# DAM16_Ethernet.net
KiCad netlist of a schematic drawn in Altium Designer
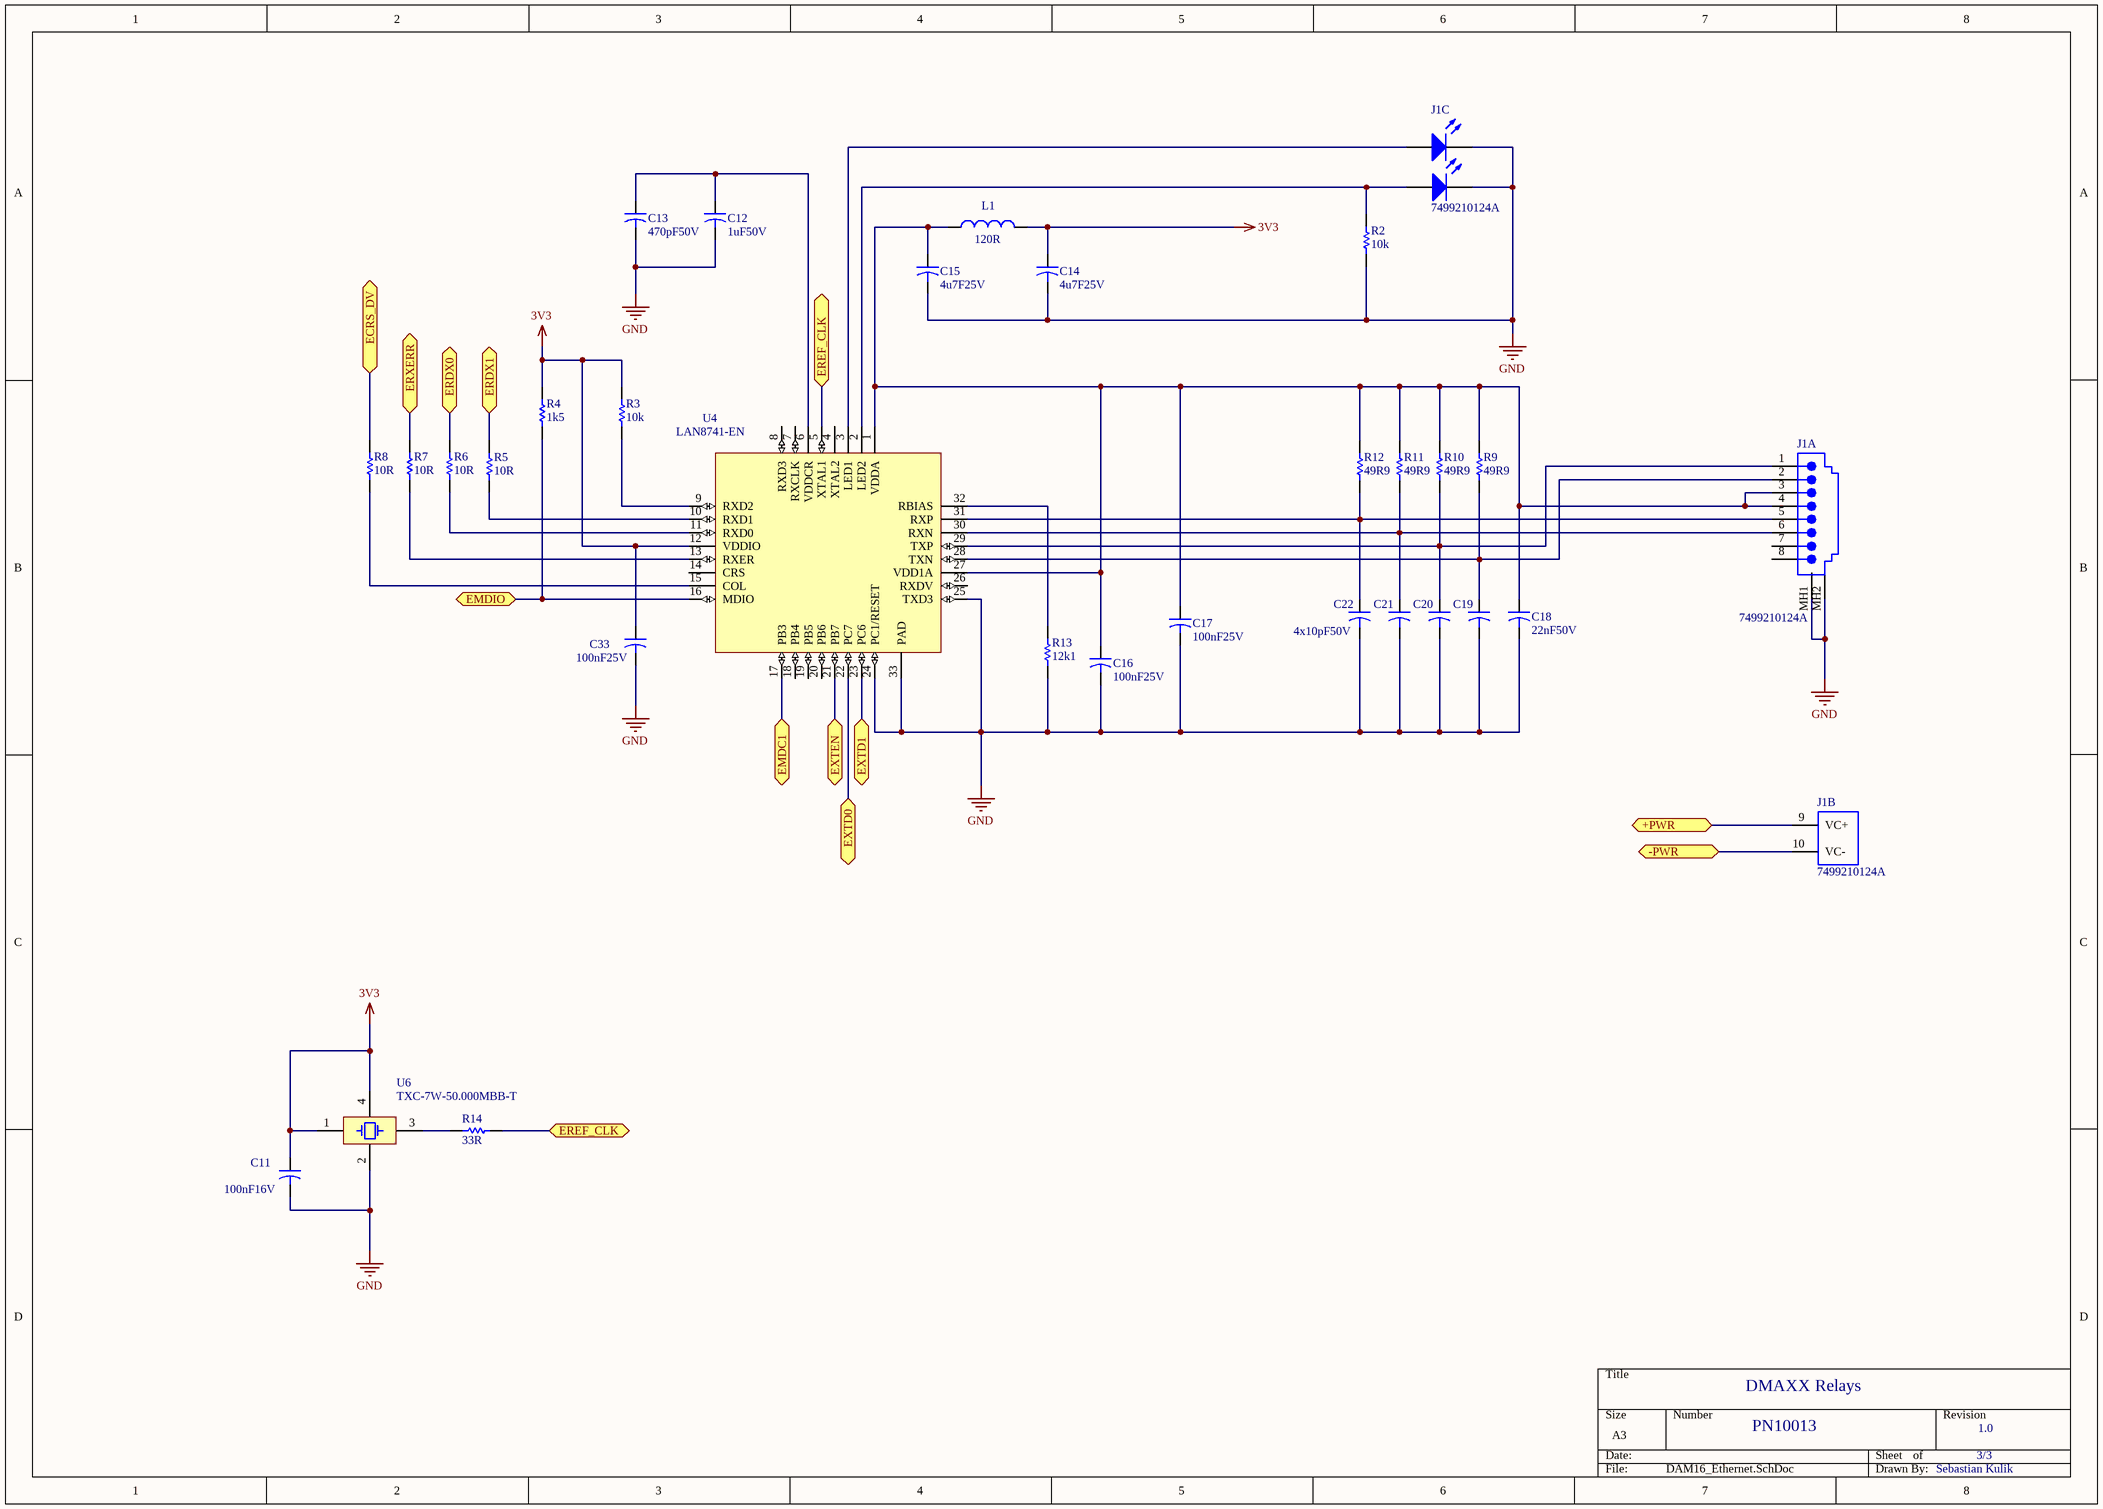
[diagram p0: DAM16_Ethernet.SchDoc]

(export (version "E")
  (design (tool "Eeschema 10.0.6"))
  (components
    (comp (ref "C11")
      (value "100nF16V")
      (footprint "C0402")
      (description "Capacitor")
      (fields
        (field (name "MANUFACTURER") "TDK")
        (field (name "Comment") "100nF16V_0402")
        (field (name "PUBLISHER") "Sebastian Kulik")
      )
      (libsource (lib "Capacitors") (part "100nF16V_0402"))
    )
    (comp (ref "C12")
      (value "1uF50V")
      (footprint "C0603")
      (description "C series, X5R, 10%")
      (fields
        (field (name "MANUFACTURER") "TDK")
        (field (name "Comment") "1uF50V_0603")
        (field (name "PUBLISHER") "Sebastian Kulik")
      )
      (libsource (lib "Capacitors") (part "1uF50V_0603"))
    )
    (comp (ref "C13")
      (value "470pF50V")
      (footprint "C0402")
      (description "AVX, 50V")
      (fields
        (field (name "MANUFACTURER") "AVX")
        (field (name "Comment") "470pF50V_0402")
        (field (name "PUBLISHER") "Sebastian Kulik")
      )
      (libsource (lib "Capacitors") (part "470pF50V_0402"))
    )
    (comp (ref "C14")
      (value "4u7F25V")
      (footprint "C0805")
      (description "TDK  C series, X7R, 10%, 25V")
      (fields
        (field (name "MANUFACTURER") "TDK")
        (field (name "Comment") "4u7F25V_0805")
        (field (name "PUBLISHER") "Sebastian Kulik")
      )
      (libsource (lib "Capacitors") (part "4u7F25V_0805"))
    )
    (comp (ref "C15")
      (value "4u7F25V")
      (footprint "C0805")
      (description "TDK  C series, X7R, 10%, 25V")
      (fields
        (field (name "MANUFACTURER") "TDK")
        (field (name "Comment") "4u7F25V_0805")
        (field (name "PUBLISHER") "Sebastian Kulik")
      )
      (libsource (lib "Capacitors") (part "4u7F25V_0805"))
    )
    (comp (ref "C16")
      (value "100nF25V")
      (footprint "C0402")
      (description "AVX, X5R, 10%, 25V")
      (fields
        (field (name "MANUFACTURER") "AVX")
        (field (name "Comment") "100nF25V_0402")
        (field (name "PUBLISHER") "Sebastian Kulik")
      )
      (libsource (lib "Capacitors") (part "100nF25V_0402"))
    )
    (comp (ref "C17")
      (value "100nF25V")
      (footprint "C0402")
      (description "AVX, X5R, 10%, 25V")
      (fields
        (field (name "MANUFACTURER") "AVX")
        (field (name "Comment") "100nF25V_0402")
        (field (name "PUBLISHER") "Sebastian Kulik")
      )
      (libsource (lib "Capacitors") (part "100nF25V_0402"))
    )
    (comp (ref "C18")
      (value "22nF50V")
      (footprint "C0603")
      (description "AVX ,  X7R, 5%, 50V")
      (fields
        (field (name "MANUFACTURER") "AVX")
        (field (name "Comment") "22nF50V_0603")
        (field (name "PUBLISHER") "Sebastian Kulik")
      )
      (libsource (lib "Capacitors") (part "22nF50V_0603"))
    )
    (comp (ref "C19")
      (value "10pF50V_0603")
      (footprint "C0603")
      (description "AVX ,  +-0.5pF, 50V")
      (fields (field (name "MANUFACTURER") "AVX") (field (name "PUBLISHER") "Sebastian Kulik"))
      (libsource (lib "Capacitors") (part "10pF50V_0603"))
    )
    (comp (ref "C20")
      (value "10pF50V_0603")
      (footprint "C0603")
      (description "AVX ,  +-0.5pF, 50V")
      (fields (field (name "MANUFACTURER") "AVX") (field (name "PUBLISHER") "Sebastian Kulik"))
      (libsource (lib "Capacitors") (part "10pF50V_0603"))
    )
    (comp (ref "C21")
      (value "10pF50V_0603")
      (footprint "C0603")
      (description "AVX ,  +-0.5pF, 50V")
      (fields (field (name "MANUFACTURER") "AVX") (field (name "PUBLISHER") "Sebastian Kulik"))
      (libsource (lib "Capacitors") (part "10pF50V_0603"))
    )
    (comp (ref "C22")
      (value "10pF50V_0603")
      (footprint "C0603")
      (description "AVX ,  +-0.5pF, 50V")
      (fields (field (name "MANUFACTURER") "AVX") (field (name "PUBLISHER") "Sebastian Kulik"))
      (libsource (lib "Capacitors") (part "10pF50V_0603"))
    )
    (comp (ref "C33")
      (value "100nF25V")
      (footprint "C0402")
      (description "AVX, X5R, 10%, 25V")
      (fields
        (field (name "MANUFACTURER") "AVX")
        (field (name "Comment") "100nF25V_0402")
        (field (name "PUBLISHER") "Sebastian Kulik")
      )
      (libsource (lib "Capacitors") (part "100nF25V_0402"))
    )
    (comp (ref "J1")
      (value "7499210124A")
      (footprint "7499210124A")
      (description "Modular Jack , Right Angle RJ-45, Low Profile")
      (fields (field (name "MANUFACTURER") "Wuerth Elektronik") (field (name "PUBLISHER") "Sebastian Kulik"))
      (libsource (lib "Connectors") (part "Ethernet, POE, WE7499210124A"))
    )
    (comp (ref "L1")
      (value "120R")
      (footprint "L0603")
      (description "Murata, Ferrit, 120Rx2A")
      (fields
        (field (name "MANUFACTURER") "Murata")
        (field (name "Comment") "120R4A_0603")
        (field (name "PUBLISHER") "Sebastian Kulik")
      )
      (libsource (lib "Passives") (part "120R4A_0603"))
    )
    (comp (ref "R2")
      (value "10k")
      (footprint "R0402")
      (description "Vishay CRCW series, 125mW, 1%")
      (fields
        (field (name "MANUFACTURER") "Vishay")
        (field (name "Comment") "10k_0402")
        (field (name "PUBLISHER") "Sebastian Kulik")
      )
      (libsource (lib "Resistors") (part "10k_0402"))
    )
    (comp (ref "R3")
      (value "10k")
      (footprint "R0402")
      (description "Vishay CRCW series, 125mW, 1%")
      (fields
        (field (name "MANUFACTURER") "Vishay")
        (field (name "Comment") "10k_0402")
        (field (name "PUBLISHER") "Sebastian Kulik")
      )
      (libsource (lib "Resistors") (part "10k_0402"))
    )
    (comp (ref "R4")
      (value "1k5")
      (footprint "R0402")
      (description "Vishay CRCW series, 125mW, 1%")
      (fields
        (field (name "MANUFACTURER") "Vishay")
        (field (name "Comment") "1k5_0402")
        (field (name "PUBLISHER") "Sebastian Kulik")
      )
      (libsource (lib "Resistors") (part "1k5_0402"))
    )
    (comp (ref "R5")
      (value "10R")
      (footprint "R0402")
      (description "Vishay CRCW series, 125mW, 1%")
      (fields
        (field (name "MANUFACTURER") "Vishay")
        (field (name "Comment") "10R_0402")
        (field (name "PUBLISHER") "Sebastian Kulik")
      )
      (libsource (lib "Resistors") (part "10R_0402"))
    )
    (comp (ref "R6")
      (value "10R")
      (footprint "R0402")
      (description "Vishay CRCW series, 125mW, 1%")
      (fields
        (field (name "MANUFACTURER") "Vishay")
        (field (name "Comment") "10R_0402")
        (field (name "PUBLISHER") "Sebastian Kulik")
      )
      (libsource (lib "Resistors") (part "10R_0402"))
    )
    (comp (ref "R7")
      (value "10R")
      (footprint "R0402")
      (description "Vishay CRCW series, 125mW, 1%")
      (fields
        (field (name "MANUFACTURER") "Vishay")
        (field (name "Comment") "10R_0402")
        (field (name "PUBLISHER") "Sebastian Kulik")
      )
      (libsource (lib "Resistors") (part "10R_0402"))
    )
    (comp (ref "R8")
      (value "10R")
      (footprint "R0402")
      (description "Vishay CRCW series, 125mW, 1%")
      (fields
        (field (name "MANUFACTURER") "Vishay")
        (field (name "Comment") "10R_0402")
        (field (name "PUBLISHER") "Sebastian Kulik")
      )
      (libsource (lib "Resistors") (part "10R_0402"))
    )
    (comp (ref "R9")
      (value "49R9")
      (footprint "R0402")
      (description "Vishay CRCW series, 63mW, 1%")
      (fields
        (field (name "MANUFACTURER") "Vishay")
        (field (name "Comment") "49R9_0402")
        (field (name "PUBLISHER") "Sebastian Kulik")
      )
      (libsource (lib "Resistors") (part "49R9_0402"))
    )
    (comp (ref "R10")
      (value "49R9")
      (footprint "R0402")
      (description "Vishay CRCW series, 63mW, 1%")
      (fields
        (field (name "MANUFACTURER") "Vishay")
        (field (name "Comment") "49R9_0402")
        (field (name "PUBLISHER") "Sebastian Kulik")
      )
      (libsource (lib "Resistors") (part "49R9_0402"))
    )
    (comp (ref "R11")
      (value "49R9")
      (footprint "R0402")
      (description "Vishay CRCW series, 63mW, 1%")
      (fields
        (field (name "MANUFACTURER") "Vishay")
        (field (name "Comment") "49R9_0402")
        (field (name "PUBLISHER") "Sebastian Kulik")
      )
      (libsource (lib "Resistors") (part "49R9_0402"))
    )
    (comp (ref "R12")
      (value "49R9")
      (footprint "R0402")
      (description "Vishay CRCW series, 63mW, 1%")
      (fields
        (field (name "MANUFACTURER") "Vishay")
        (field (name "Comment") "49R9_0402")
        (field (name "PUBLISHER") "Sebastian Kulik")
      )
      (libsource (lib "Resistors") (part "49R9_0402"))
    )
    (comp (ref "R13")
      (value "12k1")
      (footprint "R0603(1608)")
      (description "Vishay, CRCW series, 100mW, 1%")
      (fields
        (field (name "MANUFACTURER") "Vishay")
        (field (name "Comment") "12k1_0603")
        (field (name "PUBLISHER") "Sebastian Kulik")
      )
      (libsource (lib "Resistors") (part "12k1_0603"))
    )
    (comp (ref "R14")
      (value "33R")
      (footprint "R0402")
      (description "Vishay CRCW series, 63mW, 1%")
      (fields
        (field (name "MANUFACTURER") "Vishay")
        (field (name "Comment") "33R_0402")
        (field (name "PUBLISHER") "Sebastian Kulik")
      )
      (libsource (lib "Resistors") (part "33R_0402"))
    )
    (comp (ref "U4")
      (value "LAN8741-EN")
      (footprint "32M1-A_M")
      (description "Ethernet Phy")
      (fields (field (name "MANUFACTURER") "Microchip") (field (name "PUBLISHER") "Sebastian Kulik"))
      (libsource (lib "ICs") (part "LAN8741-EN"))
    )
    (comp (ref "U6")
      (value "TXC-7W-50.000MBB-T")
      (footprint "TXC_7W")
      (description "Crystal")
      (fields (field (name "MANUFACTURER") "TXC") (field (name "PUBLISHER") "Sebastian Kulik"))
      (libsource (lib "ICs") (part "TXC-7W-50.000MBB-T"))
    )
  )
  (nets
    (net (code "1") (name "/+PWR") (class "Default")
      (node (ref "J1") (pin "9") (pinfunction "VC+_9") (pintype "passive"))
    )
    (net (code "2") (name "/-PWR") (class "Default")
      (node (ref "J1") (pin "10") (pinfunction "VC-_10") (pintype "passive"))
    )
    (net (code "3") (name "/ECRS_DV") (class "Default")
      (node (ref "R8") (pin "2") (pinfunction "2_2") (pintype "passive"))
    )
    (net (code "4") (name "/EMDC1") (class "Default")
      (node (ref "U4") (pin "17") (pinfunction "PB3_17") (pintype "bidirectional"))
    )
    (net (code "5") (name "/EMDIO") (class "Default")
      (node (ref "R4") (pin "1") (pinfunction "1_1") (pintype "passive"))
      (node (ref "U4") (pin "16") (pinfunction "MDIO_16") (pintype "bidirectional"))
    )
    (net (code "6") (name "/ERDX0") (class "Default")
      (node (ref "R6") (pin "2") (pinfunction "2_2") (pintype "passive"))
    )
    (net (code "7") (name "/ERDX1") (class "Default")
      (node (ref "R5") (pin "1") (pinfunction "1_1") (pintype "passive"))
    )
    (net (code "8") (name "/EREF_CLK") (class "Default")
      (node (ref "R14") (pin "2") (pinfunction "2_2") (pintype "passive"))
      (node (ref "U4") (pin "5") (pinfunction "XTAL1_5") (pintype "bidirectional"))
    )
    (net (code "9") (name "/ERXERR") (class "Default")
      (node (ref "R7") (pin "2") (pinfunction "2_2") (pintype "passive"))
    )
    (net (code "10") (name "/EXTD0") (class "Default")
      (node (ref "U4") (pin "22") (pinfunction "PC7_22") (pintype "bidirectional"))
    )
    (net (code "11") (name "/EXTD1") (class "Default")
      (node (ref "U4") (pin "23") (pinfunction "PC6_23") (pintype "bidirectional"))
    )
    (net (code "12") (name "/EXTEN") (class "Default")
      (node (ref "U4") (pin "21") (pinfunction "PB7_21") (pintype "bidirectional"))
    )
    (net (code "13") (name "3V3") (class "Default")
      (node (ref "C11") (pin "1") (pinfunction "1_1") (pintype "passive"))
      (node (ref "C14") (pin "1") (pinfunction "1_1") (pintype "passive"))
      (node (ref "C33") (pin "1") (pinfunction "1_1") (pintype "passive"))
      (node (ref "L1") (pin "2") (pinfunction "2_2") (pintype "passive"))
      (node (ref "R3") (pin "2") (pinfunction "2_2") (pintype "passive"))
      (node (ref "R4") (pin "2") (pinfunction "2_2") (pintype "passive"))
      (node (ref "U4") (pin "12") (pinfunction "VDDIO_12") (pintype "passive"))
      (node (ref "U6") (pin "1") (pinfunction "E/D_1") (pintype "passive"))
      (node (ref "U6") (pin "4") (pinfunction "VCC_4") (pintype "passive"))
    )
    (net (code "14") (name "GND") (class "Default")
      (node (ref "C11") (pin "2") (pinfunction "2_2") (pintype "passive"))
      (node (ref "C12") (pin "2") (pinfunction "2_2") (pintype "passive"))
      (node (ref "C13") (pin "2") (pinfunction "2_2") (pintype "passive"))
      (node (ref "C14") (pin "2") (pinfunction "2_2") (pintype "passive"))
      (node (ref "C15") (pin "2") (pinfunction "2_2") (pintype "passive"))
      (node (ref "C16") (pin "2") (pinfunction "2_2") (pintype "passive"))
      (node (ref "C17") (pin "2") (pinfunction "2_2") (pintype "passive"))
      (node (ref "C18") (pin "2") (pinfunction "2_2") (pintype "passive"))
      (node (ref "C19") (pin "2") (pinfunction "2_2") (pintype "passive"))
      (node (ref "C20") (pin "2") (pinfunction "2_2") (pintype "passive"))
      (node (ref "C21") (pin "2") (pinfunction "2_2") (pintype "passive"))
      (node (ref "C22") (pin "2") (pinfunction "2_2") (pintype "passive"))
      (node (ref "C33") (pin "2") (pinfunction "2_2") (pintype "passive"))
      (node (ref "J1") (pin "11") (pinfunction "K_11") (pintype "passive"))
      (node (ref "J1") (pin "13") (pinfunction "K_13") (pintype "passive"))
      (node (ref "J1") (pin "MH1") (pinfunction "Shield_MH1") (pintype "passive"))
      (node (ref "J1") (pin "MH2") (pinfunction "Shield_MH2") (pintype "passive"))
      (node (ref "R13") (pin "1") (pinfunction "1_1") (pintype "passive"))
      (node (ref "R2") (pin "1") (pinfunction "1_1") (pintype "passive"))
      (node (ref "U4") (pin "24") (pinfunction "PC1/RESET_24") (pintype "bidirectional"))
      (node (ref "U4") (pin "25") (pinfunction "TXD3_25") (pintype "bidirectional"))
      (node (ref "U4") (pin "33") (pinfunction "PAD_33") (pintype "power_in"))
      (node (ref "U6") (pin "2") (pinfunction "GND_2") (pintype "passive"))
    )
    (net (code "15") (name "Net-(U4-COL)") (class "Default")
      (node (ref "R8") (pin "1") (pinfunction "1_1") (pintype "passive"))
      (node (ref "U4") (pin "15") (pinfunction "COL_15") (pintype "passive"))
    )
    (net (code "16") (name "Net-(U4-LED1)") (class "Default")
      (node (ref "J1") (pin "12") (pinfunction "A_12") (pintype "passive"))
      (node (ref "U4") (pin "3") (pinfunction "LED1_3") (pintype "power_in"))
    )
    (net (code "17") (name "Net-(U4-LED2)") (class "Default")
      (node (ref "J1") (pin "14") (pinfunction "A_14") (pintype "passive"))
      (node (ref "R2") (pin "2") (pinfunction "2_2") (pintype "passive"))
      (node (ref "U4") (pin "2") (pinfunction "LED2_2") (pintype "passive"))
    )
    (net (code "18") (name "Net-(U4-RBIAS)") (class "Default")
      (node (ref "R13") (pin "2") (pinfunction "2_2") (pintype "passive"))
      (node (ref "U4") (pin "32") (pinfunction "RBIAS_32") (pintype "power_in"))
    )
    (net (code "19") (name "Net-(U4-RXD0)") (class "Default")
      (node (ref "R6") (pin "1") (pinfunction "1_1") (pintype "passive"))
      (node (ref "U4") (pin "11") (pinfunction "RXD0_11") (pintype "bidirectional"))
    )
    (net (code "20") (name "Net-(U4-RXD1)") (class "Default")
      (node (ref "R5") (pin "2") (pinfunction "2_2") (pintype "passive"))
      (node (ref "U4") (pin "10") (pinfunction "RXD1_10") (pintype "bidirectional"))
    )
    (net (code "21") (name "Net-(U4-RXD2)") (class "Default")
      (node (ref "R3") (pin "1") (pinfunction "1_1") (pintype "passive"))
      (node (ref "U4") (pin "9") (pinfunction "RXD2_9") (pintype "bidirectional"))
    )
    (net (code "22") (name "Net-(U4-RXER)") (class "Default")
      (node (ref "R7") (pin "1") (pinfunction "1_1") (pintype "passive"))
      (node (ref "U4") (pin "13") (pinfunction "RXER_13") (pintype "bidirectional"))
    )
    (net (code "23") (name "Net-(U4-RXN)") (class "Default")
      (node (ref "C21") (pin "1") (pinfunction "1_1") (pintype "passive"))
      (node (ref "J1") (pin "6") (pinfunction "6_6") (pintype "passive"))
      (node (ref "R11") (pin "1") (pinfunction "1_1") (pintype "passive"))
      (node (ref "U4") (pin "30") (pinfunction "RXN_30") (pintype "passive"))
    )
    (net (code "24") (name "Net-(U4-RXP)") (class "Default")
      (node (ref "C22") (pin "1") (pinfunction "1_1") (pintype "passive"))
      (node (ref "J1") (pin "5") (pinfunction "5_5") (pintype "passive"))
      (node (ref "R12") (pin "1") (pinfunction "1_1") (pintype "passive"))
      (node (ref "U4") (pin "31") (pinfunction "RXP_31") (pintype "passive"))
    )
    (net (code "25") (name "Net-(U4-TXN)") (class "Default")
      (node (ref "C19") (pin "1") (pinfunction "1_1") (pintype "passive"))
      (node (ref "J1") (pin "2") (pinfunction "2_2") (pintype "passive"))
      (node (ref "R9") (pin "1") (pinfunction "1_1") (pintype "passive"))
      (node (ref "U4") (pin "28") (pinfunction "TXN_28") (pintype "bidirectional"))
    )
    (net (code "26") (name "Net-(U4-TXP)") (class "Default")
      (node (ref "C20") (pin "1") (pinfunction "1_1") (pintype "passive"))
      (node (ref "J1") (pin "1") (pinfunction "1_1") (pintype "passive"))
      (node (ref "R10") (pin "1") (pinfunction "1_1") (pintype "passive"))
      (node (ref "U4") (pin "29") (pinfunction "TXP_29") (pintype "bidirectional"))
    )
    (net (code "27") (name "Net-(U4-VDD1A)") (class "Default")
      (node (ref "C15") (pin "1") (pinfunction "1_1") (pintype "passive"))
      (node (ref "C16") (pin "1") (pinfunction "1_1") (pintype "passive"))
      (node (ref "C17") (pin "1") (pinfunction "1_1") (pintype "passive"))
      (node (ref "C18") (pin "1") (pinfunction "1_1") (pintype "passive"))
      (node (ref "J1") (pin "3") (pinfunction "3_3") (pintype "passive"))
      (node (ref "J1") (pin "4") (pinfunction "4_4") (pintype "passive"))
      (node (ref "L1") (pin "1") (pinfunction "1_1") (pintype "passive"))
      (node (ref "R10") (pin "2") (pinfunction "2_2") (pintype "passive"))
      (node (ref "R11") (pin "2") (pinfunction "2_2") (pintype "passive"))
      (node (ref "R12") (pin "2") (pinfunction "2_2") (pintype "passive"))
      (node (ref "R9") (pin "2") (pinfunction "2_2") (pintype "passive"))
      (node (ref "U4") (pin "1") (pinfunction "VDDA_1") (pintype "passive"))
      (node (ref "U4") (pin "27") (pinfunction "VDD1A_27") (pintype "passive"))
    )
    (net (code "28") (name "Net-(U4-VDDCR)") (class "Default")
      (node (ref "C12") (pin "1") (pinfunction "1_1") (pintype "passive"))
      (node (ref "C13") (pin "1") (pinfunction "1_1") (pintype "passive"))
      (node (ref "U4") (pin "6") (pinfunction "VDDCR_6") (pintype "passive"))
    )
    (net (code "29") (name "Net-(U6-OSC2)") (class "Default")
      (node (ref "R14") (pin "1") (pinfunction "1_1") (pintype "passive"))
      (node (ref "U6") (pin "3") (pinfunction "OSC2_3") (pintype "passive"))
    )
    (net (code "30") (name "unconnected-(J1-Pad7)") (class "Default")
      (node (ref "J1") (pin "7") (pinfunction "7_7") (pintype "passive"))
    )
    (net (code "31") (name "unconnected-(J1-Pad8)") (class "Default")
      (node (ref "J1") (pin "8") (pinfunction "8_8") (pintype "passive"))
    )
    (net (code "32") (name "unconnected-(U4-CRS-Pad14)") (class "Default")
      (node (ref "U4") (pin "14") (pinfunction "CRS_14") (pintype "passive"))
    )
    (net (code "33") (name "unconnected-(U4-PB4-Pad18)") (class "Default")
      (node (ref "U4") (pin "18") (pinfunction "PB4_18") (pintype "bidirectional"))
    )
    (net (code "34") (name "unconnected-(U4-PB5-Pad19)") (class "Default")
      (node (ref "U4") (pin "19") (pinfunction "PB5_19") (pintype "bidirectional"))
    )
    (net (code "35") (name "unconnected-(U4-PB6-Pad20)") (class "Default")
      (node (ref "U4") (pin "20") (pinfunction "PB6_20") (pintype "bidirectional"))
    )
    (net (code "36") (name "unconnected-(U4-RXCLK-Pad7)") (class "Default")
      (node (ref "U4") (pin "7") (pinfunction "RXCLK_7") (pintype "bidirectional"))
    )
    (net (code "37") (name "unconnected-(U4-RXD3-Pad8)") (class "Default")
      (node (ref "U4") (pin "8") (pinfunction "RXD3_8") (pintype "bidirectional"))
    )
    (net (code "38") (name "unconnected-(U4-RXDV-Pad26)") (class "Default")
      (node (ref "U4") (pin "26") (pinfunction "RXDV_26") (pintype "bidirectional"))
    )
    (net (code "39") (name "unconnected-(U4-XTAL2-Pad4)") (class "Default")
      (node (ref "U4") (pin "4") (pinfunction "XTAL2_4") (pintype "power_in"))
    )
  )
)
